# Adafruit_ESP8266_Feather.net
KiCad netlist of a schematic drawn in EAGLE
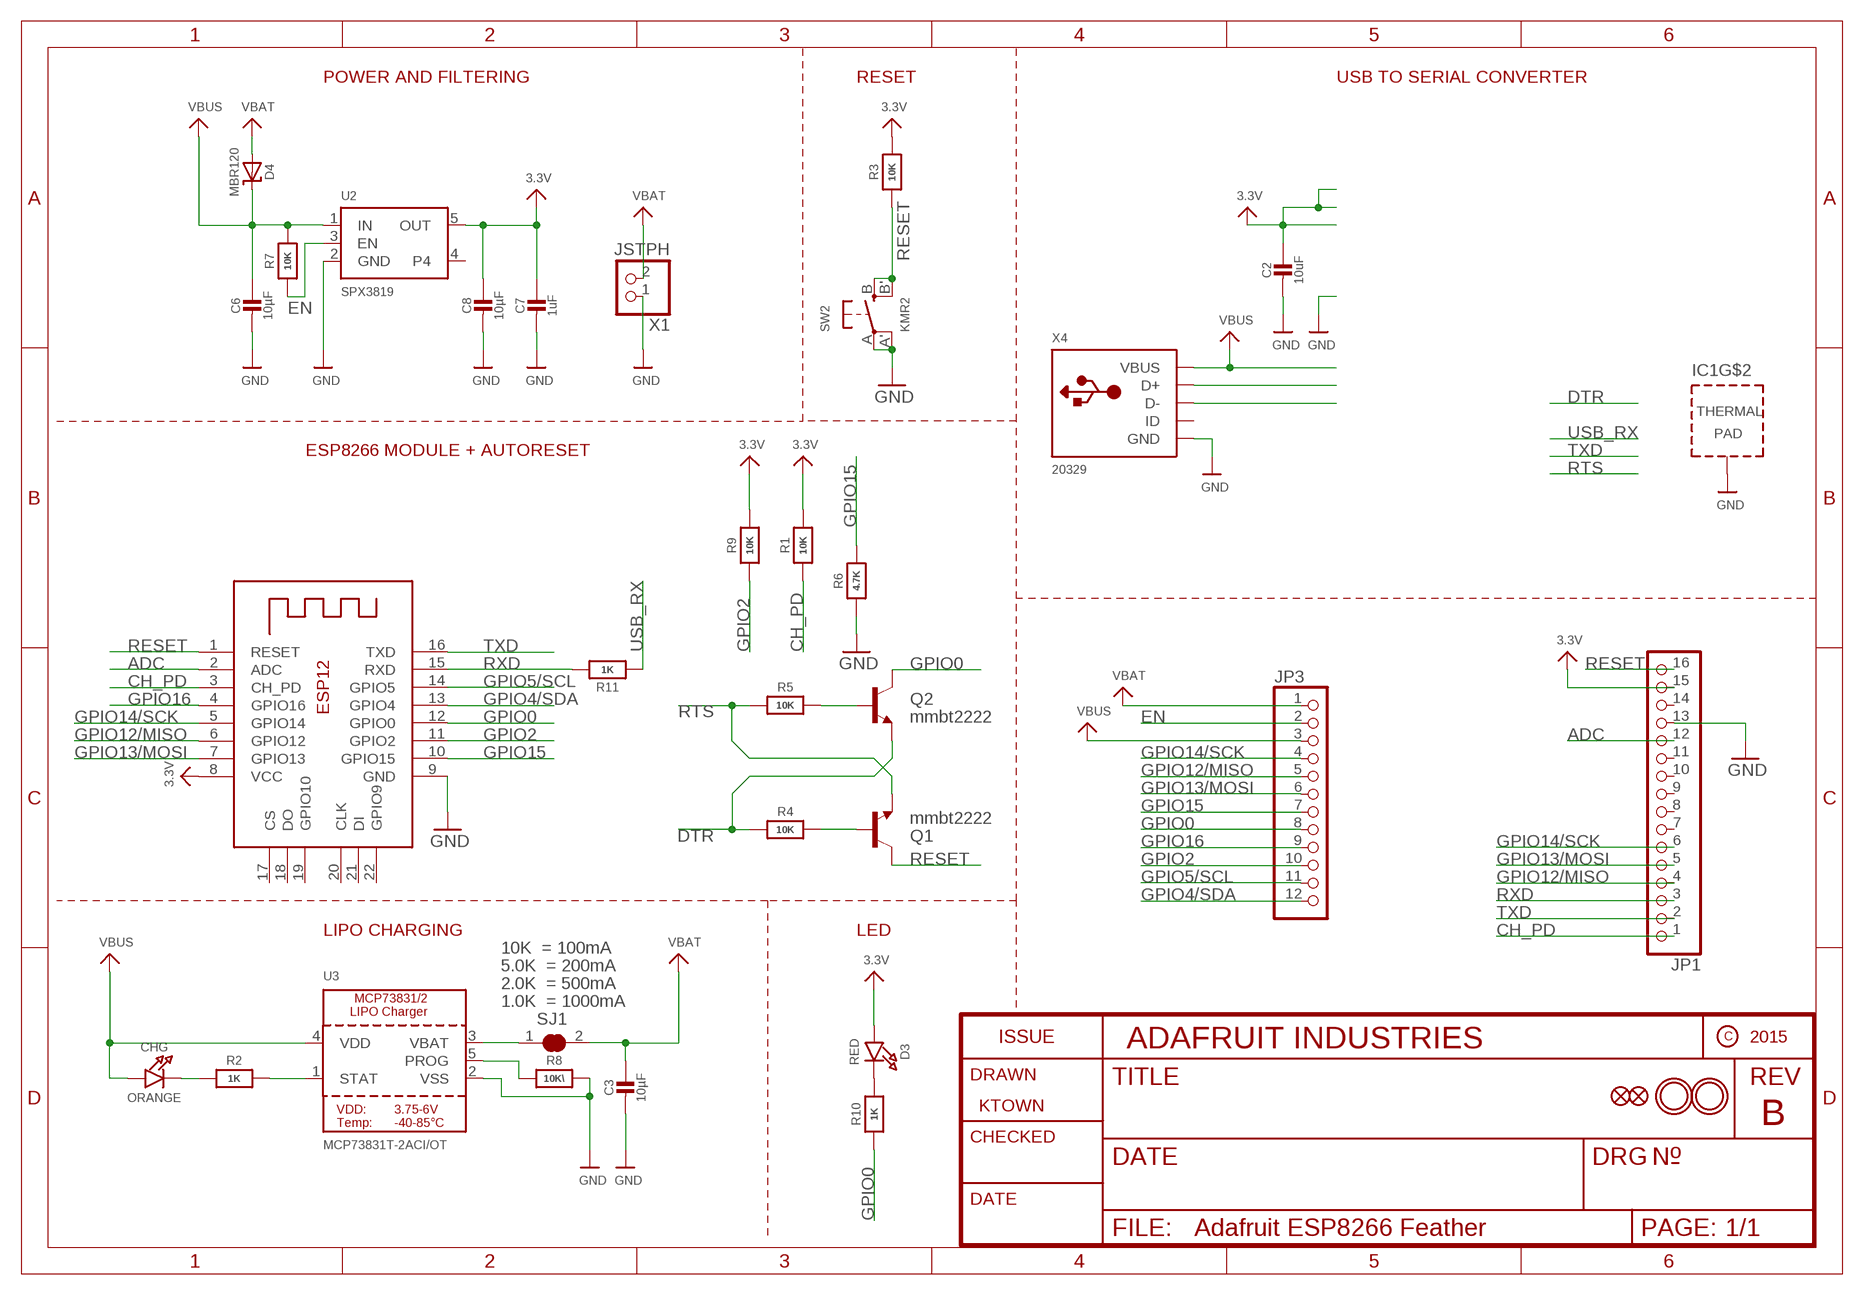
[diagram p0: schematic, sheet 1]

(export (version "E")
  (design (tool "Eeschema 10.0.6"))
  (components
    (comp (ref "C2")
      (value "10uF")
      (footprint "eagle-import:0805-NO")
      (libsource (lib "eagle-import") (part "CAP_CERAMIC0805-NOOUTLINE"))
    )
    (comp (ref "C3")
      (value "10µF")
      (footprint "eagle-import:0805-NO")
      (libsource (lib "eagle-import") (part "CAP_CERAMIC0805-NOOUTLINE"))
    )
    (comp (ref "C6")
      (value "10µF")
      (footprint "eagle-import:0805-NO")
      (libsource (lib "eagle-import") (part "CAP_CERAMIC0805-NOOUTLINE"))
    )
    (comp (ref "C7")
      (value "1uF")
      (footprint "eagle-import:0603-NO")
      (libsource (lib "eagle-import") (part "CAP_CERAMIC0603_NO"))
    )
    (comp (ref "C8")
      (value "10µF")
      (footprint "eagle-import:0805-NO")
      (libsource (lib "eagle-import") (part "CAP_CERAMIC0805-NOOUTLINE"))
    )
    (comp (ref "CHG")
      (value "ORANGE")
      (footprint "eagle-import:CHIPLED_0805_NOOUTLINE")
      (libsource (lib "eagle-import") (part "LED0805_NOOUTLINE"))
    )
    (comp (ref "D3")
      (value "RED")
      (footprint "eagle-import:CHIPLED_0805_NOOUTLINE")
      (libsource (lib "eagle-import") (part "LED0805_NOOUTLINE"))
    )
    (comp (ref "D4")
      (value "MBR120")
      (footprint "eagle-import:SOD-123")
      (libsource (lib "eagle-import") (part "DIODE-SCHOTTKYSOD-123"))
    )
    (comp (ref "IC1")
      (value "CP2104")
      (footprint "eagle-import:QFN24_4MM_SMSC")
      (libsource (lib "eagle-import") (part "CP2104"))
    )
    (comp (ref "JP1")
      (value "HEADER-1X16ROUND")
      (footprint "eagle-import:1X16_ROUND")
      (libsource (lib "eagle-import") (part "HEADER-1X16ROUND"))
    )
    (comp (ref "JP3")
      (value "HEADER-1X12")
      (footprint "eagle-import:1X12_ROUND")
      (libsource (lib "eagle-import") (part "HEADER-1X12"))
    )
    (comp (ref "Q1")
      (value "mmbt2222")
      (footprint "eagle-import:SOT23-3")
      (libsource (lib "eagle-import") (part "TRANSISTOR_NPNSOT23-3"))
    )
    (comp (ref "Q2")
      (value "mmbt2222")
      (footprint "eagle-import:SOT23-3")
      (libsource (lib "eagle-import") (part "TRANSISTOR_NPNSOT23-3"))
    )
    (comp (ref "R1")
      (value "10K")
      (footprint "eagle-import:0603-NO")
      (libsource (lib "eagle-import") (part "RESISTOR_0603_NOOUT"))
    )
    (comp (ref "R2")
      (value "1K")
      (footprint "eagle-import:0603-NO")
      (libsource (lib "eagle-import") (part "RESISTOR_0603_NOOUT"))
    )
    (comp (ref "R3")
      (value "10K")
      (footprint "eagle-import:0603-NO")
      (libsource (lib "eagle-import") (part "RESISTOR_0603_NOOUT"))
    )
    (comp (ref "R4")
      (value "10K")
      (footprint "eagle-import:0603-NO")
      (libsource (lib "eagle-import") (part "RESISTOR_0603_NOOUT"))
    )
    (comp (ref "R5")
      (value "10K")
      (footprint "eagle-import:_0603MP")
      (libsource (lib "eagle-import") (part "RESISTOR_0603MP"))
    )
    (comp (ref "R6")
      (value "4.7K")
      (footprint "eagle-import:0603-NO")
      (libsource (lib "eagle-import") (part "RESISTOR_0603_NOOUT"))
    )
    (comp (ref "R7")
      (value "10K")
      (footprint "eagle-import:0603-NO")
      (libsource (lib "eagle-import") (part "RESISTOR_0603_NOOUT"))
    )
    (comp (ref "R8")
      (value "10K\\")
      (footprint "eagle-import:0603-NO")
      (libsource (lib "eagle-import") (part "RESISTOR_0603_NOOUT"))
    )
    (comp (ref "R9")
      (value "10K")
      (footprint "eagle-import:0603-NO")
      (libsource (lib "eagle-import") (part "RESISTOR_0603_NOOUT"))
    )
    (comp (ref "R10")
      (value "1K")
      (footprint "eagle-import:0603-NO")
      (libsource (lib "eagle-import") (part "RESISTOR_0603_NOOUT"))
    )
    (comp (ref "R11")
      (value "1K")
      (footprint "eagle-import:_0603MP")
      (libsource (lib "eagle-import") (part "RESISTOR_0603MP"))
    )
    (comp (ref "SJ1")
      (value "SOLDERJUMPER_CLOSED")
      (footprint "eagle-import:SOLDERJUMPER_CLOSEDWIRE")
      (libsource (lib "eagle-import") (part "SOLDERJUMPER_CLOSED"))
    )
    (comp (ref "SW2")
      (value "KMR2")
      (footprint "eagle-import:BTN_KMR2_4.6X2.8")
      (libsource (lib "eagle-import") (part "SWITCH_TACT_SMT4.6X2.8"))
    )
    (comp (ref "U$31")
      (value "MOUNTINGHOLE2.5")
      (footprint "eagle-import:MOUNTINGHOLE_2.5_PLATED")
      (libsource (lib "eagle-import") (part "MOUNTINGHOLE2.5"))
    )
    (comp (ref "U$32")
      (value "MOUNTINGHOLE2.5")
      (footprint "eagle-import:MOUNTINGHOLE_2.5_PLATED")
      (libsource (lib "eagle-import") (part "MOUNTINGHOLE2.5"))
    )
    (comp (ref "U$34")
      (value "FIDUCIAL\"\"")
      (footprint "eagle-import:FIDUCIAL_1MM")
      (libsource (lib "eagle-import") (part "FIDUCIAL{dblquote}{dblquote}"))
    )
    (comp (ref "U$35")
      (value "FIDUCIAL\"\"")
      (footprint "eagle-import:FIDUCIAL_1MM")
      (libsource (lib "eagle-import") (part "FIDUCIAL{dblquote}{dblquote}"))
    )
    (comp (ref "U2")
      (value "SPX3819")
      (footprint "eagle-import:SOT23-5")
      (libsource (lib "eagle-import") (part "VREG_SOT23-5"))
    )
    (comp (ref "U3")
      (value "MCP73831T-2ACI/OT")
      (footprint "eagle-import:SOT23-5")
      (libsource (lib "eagle-import") (part "MCP73831/2"))
    )
    (comp (ref "X1")
      (value "JSTPH")
      (footprint "eagle-import:JSTPH2")
      (libsource (lib "eagle-import") (part "CON_JST_PH_2PIN"))
    )
    (comp (ref "X2")
      (value "ESP-12")
      (footprint "eagle-import:ESP-12E")
      (libsource (lib "eagle-import") (part "ESP-12E"))
    )
    (comp (ref "X4")
      (value "20329")
      (footprint "eagle-import:4UCONN_20329_V2")
      (libsource (lib "eagle-import") (part "USB_MICRO_20329_V2"))
    )
  )
  (nets
    (net (code "1") (name "/ADC") (class "Default")
      (node (ref "JP1") (pin "12") (pinfunction "12_12") (pintype "passive"))
      (node (ref "X2") (pin "2") (pinfunction "ADC_2") (pintype "passive"))
    )
    (net (code "2") (name "/CH_PD") (class "Default")
      (node (ref "JP1") (pin "1") (pinfunction "1_1") (pintype "passive"))
      (node (ref "R1") (pin "1") (pinfunction "1_1") (pintype "passive"))
      (node (ref "X2") (pin "3") (pinfunction "CH_PD_3") (pintype "input"))
    )
    (net (code "3") (name "/DTR") (class "Default")
      (node (ref "Q2") (pin "2") (pinfunction "E_2") (pintype "passive"))
      (node (ref "R4") (pin "1") (pinfunction "1_1") (pintype "passive"))
    )
    (net (code "4") (name "/EN") (class "Default")
      (node (ref "JP3") (pin "2") (pinfunction "2_2") (pintype "passive"))
      (node (ref "R7") (pin "1") (pinfunction "1_1") (pintype "passive"))
      (node (ref "U2") (pin "3") (pinfunction "EN_3") (pintype "input"))
    )
    (net (code "5") (name "/GPIO0") (class "Default")
      (node (ref "JP3") (pin "8") (pinfunction "8_8") (pintype "passive"))
      (node (ref "Q2") (pin "3") (pinfunction "C_3") (pintype "passive"))
      (node (ref "R10") (pin "1") (pinfunction "1_1") (pintype "passive"))
      (node (ref "X2") (pin "12") (pinfunction "GPIO0_12") (pintype "bidirectional"))
    )
    (net (code "6") (name "/GPIO2") (class "Default")
      (node (ref "JP3") (pin "10") (pinfunction "10_10") (pintype "passive"))
      (node (ref "R9") (pin "1") (pinfunction "1_1") (pintype "passive"))
      (node (ref "X2") (pin "11") (pinfunction "GPIO2_11") (pintype "bidirectional"))
    )
    (net (code "7") (name "/GPIO4{slash}SDA") (class "Default")
      (node (ref "JP3") (pin "12") (pinfunction "12_12") (pintype "passive"))
      (node (ref "X2") (pin "13") (pinfunction "GPIO4_13") (pintype "bidirectional"))
    )
    (net (code "8") (name "/GPIO5{slash}SCL") (class "Default")
      (node (ref "JP3") (pin "11") (pinfunction "11_11") (pintype "passive"))
      (node (ref "X2") (pin "14") (pinfunction "GPIO5_14") (pintype "bidirectional"))
    )
    (net (code "9") (name "/GPIO12{slash}MISO") (class "Default")
      (node (ref "JP1") (pin "4") (pinfunction "4_4") (pintype "passive"))
      (node (ref "JP3") (pin "5") (pinfunction "5_5") (pintype "passive"))
      (node (ref "X2") (pin "6") (pinfunction "GPIO12_6") (pintype "bidirectional"))
    )
    (net (code "10") (name "/GPIO13{slash}MOSI") (class "Default")
      (node (ref "JP1") (pin "5") (pinfunction "5_5") (pintype "passive"))
      (node (ref "JP3") (pin "6") (pinfunction "6_6") (pintype "passive"))
      (node (ref "X2") (pin "7") (pinfunction "GPIO13_7") (pintype "bidirectional"))
    )
    (net (code "11") (name "/GPIO14{slash}SCK") (class "Default")
      (node (ref "JP1") (pin "6") (pinfunction "6_6") (pintype "passive"))
      (node (ref "JP3") (pin "4") (pinfunction "4_4") (pintype "passive"))
      (node (ref "X2") (pin "5") (pinfunction "GPIO14_5") (pintype "bidirectional"))
    )
    (net (code "12") (name "/GPIO15") (class "Default")
      (node (ref "JP3") (pin "7") (pinfunction "7_7") (pintype "passive"))
      (node (ref "R6") (pin "2") (pinfunction "2_2") (pintype "passive"))
      (node (ref "X2") (pin "10") (pinfunction "GPIO15_10") (pintype "bidirectional"))
    )
    (net (code "13") (name "/GPIO16") (class "Default")
      (node (ref "JP3") (pin "9") (pinfunction "9_9") (pintype "passive"))
      (node (ref "X2") (pin "4") (pinfunction "GPIO16_4") (pintype "bidirectional"))
    )
    (net (code "14") (name "/RESET") (class "Default")
      (node (ref "JP1") (pin "16") (pinfunction "16_16") (pintype "passive"))
      (node (ref "Q1") (pin "3") (pinfunction "C_3") (pintype "passive"))
      (node (ref "R3") (pin "1") (pinfunction "1_1") (pintype "passive"))
      (node (ref "SW2") (pin "B") (pinfunction "S_B") (pintype "passive"))
      (node (ref "SW2") (pin "B'") (pinfunction "S1_B'") (pintype "passive"))
      (node (ref "X2") (pin "1") (pinfunction "RESET_1") (pintype "input"))
    )
    (net (code "15") (name "/RTS") (class "Default")
      (node (ref "Q1") (pin "2") (pinfunction "E_2") (pintype "passive"))
      (node (ref "R5") (pin "1") (pinfunction "1_1") (pintype "passive"))
    )
    (net (code "16") (name "/RXD") (class "Default")
      (node (ref "JP1") (pin "3") (pinfunction "3_3") (pintype "passive"))
      (node (ref "R11") (pin "2") (pinfunction "2_2") (pintype "passive"))
      (node (ref "X2") (pin "15") (pinfunction "RXD_15") (pintype "input"))
    )
    (net (code "17") (name "/TXD") (class "Default")
      (node (ref "JP1") (pin "2") (pinfunction "2_2") (pintype "passive"))
      (node (ref "X2") (pin "16") (pinfunction "TXD_16") (pintype "output"))
    )
    (net (code "18") (name "/USB_RX") (class "Default")
      (node (ref "R11") (pin "1") (pinfunction "1_1") (pintype "passive"))
    )
    (net (code "19") (name "3.3V") (class "Default")
      (node (ref "C2") (pin "1") (pinfunction "1_1") (pintype "passive"))
      (node (ref "C7") (pin "1") (pinfunction "1_1") (pintype "passive"))
      (node (ref "C8") (pin "1") (pinfunction "1_1") (pintype "passive"))
      (node (ref "D3") (pin "A") (pinfunction "A_A") (pintype "passive"))
      (node (ref "JP1") (pin "15") (pinfunction "15_15") (pintype "passive"))
      (node (ref "R1") (pin "2") (pinfunction "2_2") (pintype "passive"))
      (node (ref "R3") (pin "2") (pinfunction "2_2") (pintype "passive"))
      (node (ref "R9") (pin "2") (pinfunction "2_2") (pintype "passive"))
      (node (ref "U2") (pin "5") (pinfunction "OUT_5") (pintype "power_in"))
      (node (ref "X2") (pin "8") (pinfunction "VCC_8") (pintype "power_in"))
    )
    (net (code "20") (name "GND") (class "Default")
      (node (ref "C2") (pin "2") (pinfunction "2_2") (pintype "passive"))
      (node (ref "C3") (pin "2") (pinfunction "2_2") (pintype "passive"))
      (node (ref "C6") (pin "2") (pinfunction "2_2") (pintype "passive"))
      (node (ref "C7") (pin "2") (pinfunction "2_2") (pintype "passive"))
      (node (ref "C8") (pin "2") (pinfunction "2_2") (pintype "passive"))
      (node (ref "IC1") (pin "THERM") (pinfunction "TP_THERM") (pintype "power_in"))
      (node (ref "JP1") (pin "13") (pinfunction "13_13") (pintype "passive"))
      (node (ref "R6") (pin "1") (pinfunction "1_1") (pintype "passive"))
      (node (ref "R8") (pin "2") (pinfunction "2_2") (pintype "passive"))
      (node (ref "SW2") (pin "A") (pinfunction "P_A") (pintype "passive"))
      (node (ref "SW2") (pin "A'") (pinfunction "P1_A'") (pintype "passive"))
      (node (ref "U2") (pin "2") (pinfunction "GND_2") (pintype "power_in"))
      (node (ref "U3") (pin "2") (pinfunction "VSS_2") (pintype "power_in"))
      (node (ref "X1") (pin "1") (pinfunction "1_1") (pintype "passive"))
      (node (ref "X2") (pin "9") (pinfunction "GND_9") (pintype "power_in"))
      (node (ref "X4") (pin "BASE@1") (pinfunction "GND_BASE@1") (pintype "power_in"))
      (node (ref "X4") (pin "BASE@2") (pinfunction "GND_BASE@2") (pintype "power_in"))
      (node (ref "X4") (pin "GND") (pinfunction "GND_GND") (pintype "power_in"))
      (node (ref "X4") (pin "SPRT@1") (pinfunction "GND_SPRT@1") (pintype "power_in"))
      (node (ref "X4") (pin "SPRT@2") (pinfunction "GND_SPRT@2") (pintype "power_in"))
      (node (ref "X4") (pin "SPRT@3") (pinfunction "GND_SPRT@3") (pintype "power_in"))
      (node (ref "X4") (pin "SPRT@4") (pinfunction "GND_SPRT@4") (pintype "power_in"))
    )
    (net (code "21") (name "Net-(CHG-PadC)") (class "Default")
      (node (ref "CHG") (pin "C") (pinfunction "C_C") (pintype "passive"))
      (node (ref "R2") (pin "1") (pinfunction "1_1") (pintype "passive"))
    )
    (net (code "22") (name "Net-(D3-PadC)") (class "Default")
      (node (ref "D3") (pin "C") (pinfunction "C_C") (pintype "passive"))
      (node (ref "R10") (pin "2") (pinfunction "2_2") (pintype "passive"))
    )
    (net (code "23") (name "Net-(Q1-B)") (class "Default")
      (node (ref "Q1") (pin "1") (pinfunction "B_1") (pintype "passive"))
      (node (ref "R4") (pin "2") (pinfunction "2_2") (pintype "passive"))
    )
    (net (code "24") (name "Net-(Q2-B)") (class "Default")
      (node (ref "Q2") (pin "1") (pinfunction "B_1") (pintype "passive"))
      (node (ref "R5") (pin "2") (pinfunction "2_2") (pintype "passive"))
    )
    (net (code "25") (name "Net-(U3-PROG)") (class "Default")
      (node (ref "R8") (pin "1") (pinfunction "1_1") (pintype "passive"))
      (node (ref "U3") (pin "5") (pinfunction "PROG_5") (pintype "input"))
    )
    (net (code "26") (name "Net-(U3-STAT)") (class "Default")
      (node (ref "R2") (pin "2") (pinfunction "2_2") (pintype "passive"))
      (node (ref "U3") (pin "1") (pinfunction "STAT_1") (pintype "output"))
    )
    (net (code "27") (name "Net-(U3-VBAT)") (class "Default")
      (node (ref "SJ1") (pin "1") (pinfunction "1_1") (pintype "passive"))
      (node (ref "U3") (pin "3") (pinfunction "VBAT_3") (pintype "power_in"))
    )
    (net (code "28") (name "VBAT") (class "Default")
      (node (ref "C3") (pin "1") (pinfunction "1_1") (pintype "passive"))
      (node (ref "D4") (pin "A") (pinfunction "A_A") (pintype "passive"))
      (node (ref "JP3") (pin "1") (pinfunction "1_1") (pintype "passive"))
      (node (ref "SJ1") (pin "2") (pinfunction "2_2") (pintype "passive"))
      (node (ref "X1") (pin "2") (pinfunction "2_2") (pintype "passive"))
    )
    (net (code "29") (name "VBUS") (class "Default")
      (node (ref "C6") (pin "1") (pinfunction "1_1") (pintype "passive"))
      (node (ref "CHG") (pin "A") (pinfunction "A_A") (pintype "passive"))
      (node (ref "D4") (pin "C") (pinfunction "C_C") (pintype "passive"))
      (node (ref "JP3") (pin "3") (pinfunction "3_3") (pintype "passive"))
      (node (ref "R7") (pin "2") (pinfunction "2_2") (pintype "passive"))
      (node (ref "U2") (pin "1") (pinfunction "IN_1") (pintype "power_in"))
      (node (ref "U3") (pin "4") (pinfunction "VDD_4") (pintype "power_in"))
      (node (ref "X4") (pin "VBUS") (pinfunction "VBUS_VBUS") (pintype "power_in"))
    )
    (net (code "30") (name "unconnected-(JP1-Pad7)") (class "Default")
      (node (ref "JP1") (pin "7") (pinfunction "7_7") (pintype "passive"))
    )
    (net (code "31") (name "unconnected-(JP1-Pad8)") (class "Default")
      (node (ref "JP1") (pin "8") (pinfunction "8_8") (pintype "passive"))
    )
    (net (code "32") (name "unconnected-(JP1-Pad9)") (class "Default")
      (node (ref "JP1") (pin "9") (pinfunction "9_9") (pintype "passive"))
    )
    (net (code "33") (name "unconnected-(JP1-Pad10)") (class "Default")
      (node (ref "JP1") (pin "10") (pinfunction "10_10") (pintype "passive"))
    )
    (net (code "34") (name "unconnected-(JP1-Pad11)") (class "Default")
      (node (ref "JP1") (pin "11") (pinfunction "11_11") (pintype "passive"))
    )
    (net (code "35") (name "unconnected-(JP1-Pad14)") (class "Default")
      (node (ref "JP1") (pin "14") (pinfunction "14_14") (pintype "passive"))
    )
    (net (code "36") (name "unconnected-(U2-P4-Pad4)") (class "Default")
      (node (ref "U2") (pin "4") (pinfunction "P4_4") (pintype "bidirectional"))
    )
    (net (code "37") (name "unconnected-(X2-CLK-Pad20)") (class "Default")
      (node (ref "X2") (pin "20") (pinfunction "CLK_20") (pintype "bidirectional"))
    )
    (net (code "38") (name "unconnected-(X2-CS-Pad17)") (class "Default")
      (node (ref "X2") (pin "17") (pinfunction "CS_17") (pintype "bidirectional"))
    )
    (net (code "39") (name "unconnected-(X2-DI-Pad21)") (class "Default")
      (node (ref "X2") (pin "21") (pinfunction "DI_21") (pintype "bidirectional"))
    )
    (net (code "40") (name "unconnected-(X2-DO-Pad18)") (class "Default")
      (node (ref "X2") (pin "18") (pinfunction "DO_18") (pintype "bidirectional"))
    )
    (net (code "41") (name "unconnected-(X2-GPIO9-Pad22)") (class "Default")
      (node (ref "X2") (pin "22") (pinfunction "GPIO9_22") (pintype "bidirectional"))
    )
    (net (code "42") (name "unconnected-(X2-GPIO10-Pad19)") (class "Default")
      (node (ref "X2") (pin "19") (pinfunction "GPIO10_19") (pintype "bidirectional"))
    )
    (net (code "43") (name "unconnected-(X4-PadD+)") (class "Default")
      (node (ref "X4") (pin "D+") (pinfunction "D+_D+") (pintype "bidirectional"))
    )
    (net (code "44") (name "unconnected-(X4-PadD-)") (class "Default")
      (node (ref "X4") (pin "D-") (pinfunction "D-_D-") (pintype "bidirectional"))
    )
    (net (code "45") (name "unconnected-(X4-PadID)") (class "Default")
      (node (ref "X4") (pin "ID") (pinfunction "ID_ID") (pintype "bidirectional"))
    )
  )
)
